# bikeSensor.net
KiCad netlist of a schematic drawn in EAGLE
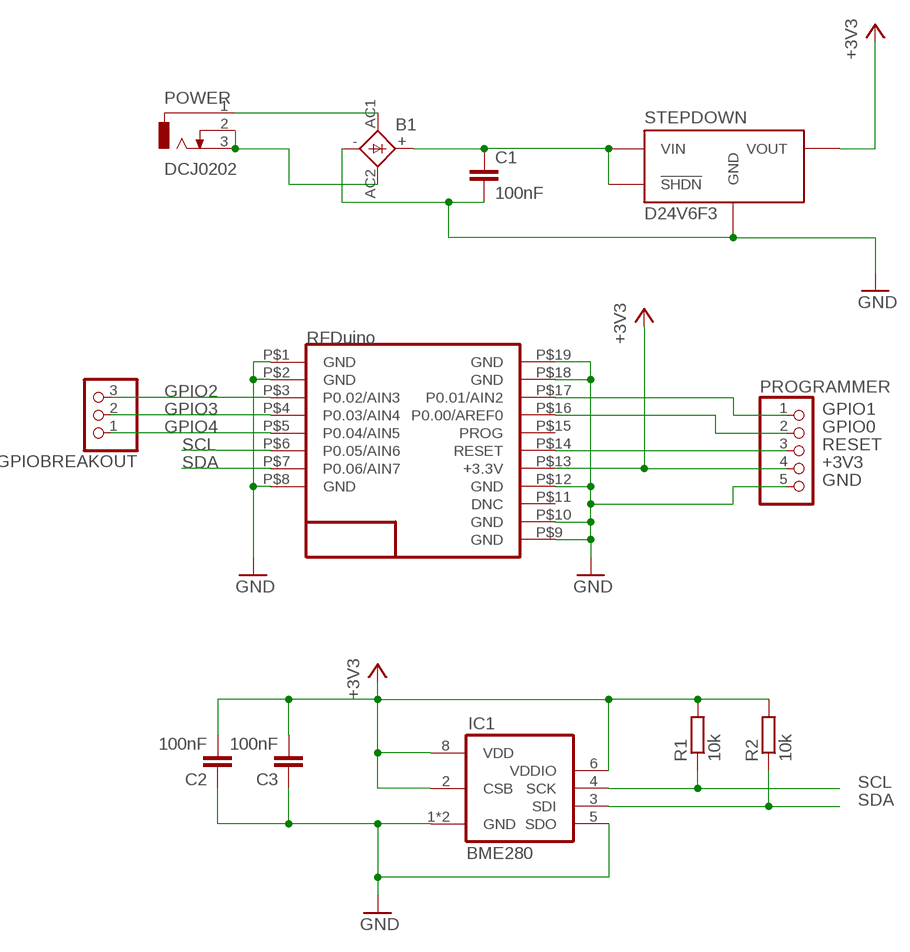
[diagram p0: schematic, sheet 1]

(export (version "E")
  (design (tool "Eeschema 10.0.6"))
  (components
    (comp (ref "B1")
      (value "1KAB")
      (footprint "eagle-import:1KAB")
      (libsource (lib "eagle-import") (part "1KAB"))
    )
    (comp (ref "C1")
      (value "100nF")
      (footprint "eagle-import:C025-050X050")
      (libsource (lib "eagle-import") (part "C-EU025-050X050"))
    )
    (comp (ref "C2")
      (value "100nF")
      (footprint "eagle-import:C1812")
      (libsource (lib "eagle-import") (part "C-EUC1812"))
    )
    (comp (ref "C3")
      (value "100nF")
      (footprint "eagle-import:C1812")
      (libsource (lib "eagle-import") (part "C-EUC1812"))
    )
    (comp (ref "GPIOBREAKOUT")
      (value "PINHD-1X3")
      (footprint "eagle-import:1X03")
      (libsource (lib "eagle-import") (part "PINHD-1X3"))
    )
    (comp (ref "IC1")
      (value "BME280")
      (footprint "eagle-import:BME280")
      (libsource (lib "eagle-import") (part "BME280"))
    )
    (comp (ref "POWER")
      (value "DCJ0202")
      (footprint "eagle-import:DCJ0202")
      (libsource (lib "eagle-import") (part "DCJ0202"))
    )
    (comp (ref "PROGRAMMER")
      (value "PINHD-1X5")
      (footprint "eagle-import:1X05")
      (libsource (lib "eagle-import") (part "PINHD-1X5"))
    )
    (comp (ref "R1")
      (value "10k")
      (footprint "eagle-import:R1206")
      (libsource (lib "eagle-import") (part "R-EU_R1206"))
    )
    (comp (ref "R2")
      (value "10k")
      (footprint "eagle-import:R1206")
      (libsource (lib "eagle-import") (part "R-EU_R1206"))
    )
    (comp (ref "RFDUINO")
      (value "RFD22301")
      (footprint "eagle-import:RFD21733")
      (libsource (lib "eagle-import") (part "RFD22301"))
    )
    (comp (ref "STEPDOWN")
      (value "D24V6F3")
      (footprint "eagle-import:D24V6F3")
      (libsource (lib "eagle-import") (part "D24V6F3"))
    )
  )
  (nets
    (net (code "1") (name "+3V3") (class "Default")
      (node (ref "C2") (pin "2") (pinfunction "2_2") (pintype "passive"))
      (node (ref "C3") (pin "2") (pinfunction "2_2") (pintype "passive"))
      (node (ref "IC1") (pin "2") (pinfunction "CSB_2") (pintype "input"))
      (node (ref "IC1") (pin "6") (pinfunction "VDDIO_6") (pintype "power_in"))
      (node (ref "IC1") (pin "8") (pinfunction "VDD_8") (pintype "power_in"))
      (node (ref "PROGRAMMER") (pin "4") (pinfunction "4_4") (pintype "passive"))
      (node (ref "R1") (pin "2") (pinfunction "2_2") (pintype "passive"))
      (node (ref "R2") (pin "2") (pinfunction "2_2") (pintype "passive"))
      (node (ref "RFDUINO") (pin "P$13") (pinfunction "+3.3V_P$13") (pintype "bidirectional"))
      (node (ref "STEPDOWN") (pin "VOUT") (pinfunction "VOUT_VOUT") (pintype "bidirectional"))
    )
    (net (code "2") (name "/GPIO0") (class "Default")
      (node (ref "PROGRAMMER") (pin "2") (pinfunction "2_2") (pintype "passive"))
      (node (ref "RFDUINO") (pin "P$16") (pinfunction "P0.00/AREF0_P$16") (pintype "bidirectional"))
    )
    (net (code "3") (name "/GPIO1") (class "Default")
      (node (ref "PROGRAMMER") (pin "1") (pinfunction "1_1") (pintype "passive"))
      (node (ref "RFDUINO") (pin "P$17") (pinfunction "P0.01/AIN2_P$17") (pintype "bidirectional"))
    )
    (net (code "4") (name "/GPIO2") (class "Default")
      (node (ref "GPIOBREAKOUT") (pin "3") (pinfunction "3_3") (pintype "passive"))
      (node (ref "RFDUINO") (pin "P$3") (pinfunction "P0.02/AIN3_P$3") (pintype "bidirectional"))
    )
    (net (code "5") (name "/GPIO3") (class "Default")
      (node (ref "GPIOBREAKOUT") (pin "2") (pinfunction "2_2") (pintype "passive"))
      (node (ref "RFDUINO") (pin "P$4") (pinfunction "P0.03/AIN4_P$4") (pintype "bidirectional"))
    )
    (net (code "6") (name "/GPIO4") (class "Default")
      (node (ref "GPIOBREAKOUT") (pin "1") (pinfunction "1_1") (pintype "passive"))
      (node (ref "RFDUINO") (pin "P$5") (pinfunction "P0.04/AIN5_P$5") (pintype "bidirectional"))
    )
    (net (code "7") (name "/RESET") (class "Default")
      (node (ref "PROGRAMMER") (pin "3") (pinfunction "3_3") (pintype "passive"))
      (node (ref "RFDUINO") (pin "P$14") (pinfunction "RESET_P$14") (pintype "bidirectional"))
    )
    (net (code "8") (name "/SCL") (class "Default")
      (node (ref "IC1") (pin "4") (pinfunction "SCK_4") (pintype "bidirectional"))
      (node (ref "R1") (pin "1") (pinfunction "1_1") (pintype "passive"))
      (node (ref "RFDUINO") (pin "P$6") (pinfunction "P0.05/AIN6_P$6") (pintype "bidirectional"))
    )
    (net (code "9") (name "/SDA") (class "Default")
      (node (ref "IC1") (pin "3") (pinfunction "SDI_3") (pintype "bidirectional"))
      (node (ref "R2") (pin "1") (pinfunction "1_1") (pintype "passive"))
      (node (ref "RFDUINO") (pin "P$7") (pinfunction "P0.06/AIN7_P$7") (pintype "bidirectional"))
    )
    (net (code "10") (name "GND") (class "Default")
      (node (ref "B1") (pin "-") (pinfunction "-_-") (pintype "passive"))
      (node (ref "C1") (pin "2") (pinfunction "2_2") (pintype "passive"))
      (node (ref "C2") (pin "1") (pinfunction "1_1") (pintype "passive"))
      (node (ref "C3") (pin "1") (pinfunction "1_1") (pintype "passive"))
      (node (ref "IC1") (pin "1") (pinfunction "GND_1") (pintype "power_in"))
      (node (ref "IC1") (pin "5") (pinfunction "SDO_5") (pintype "input"))
      (node (ref "IC1") (pin "7") (pinfunction "GND_7") (pintype "power_in"))
      (node (ref "PROGRAMMER") (pin "5") (pinfunction "5_5") (pintype "passive"))
      (node (ref "RFDUINO") (pin "P$1") (pinfunction "GND_P$1") (pintype "bidirectional"))
      (node (ref "RFDUINO") (pin "P$10") (pinfunction "GND_P$10") (pintype "bidirectional"))
      (node (ref "RFDUINO") (pin "P$12") (pinfunction "GND_P$12") (pintype "bidirectional"))
      (node (ref "RFDUINO") (pin "P$18") (pinfunction "GND_P$18") (pintype "bidirectional"))
      (node (ref "RFDUINO") (pin "P$19") (pinfunction "GND_P$19") (pintype "bidirectional"))
      (node (ref "RFDUINO") (pin "P$2") (pinfunction "GND_P$2") (pintype "bidirectional"))
      (node (ref "RFDUINO") (pin "P$8") (pinfunction "GND_P$8") (pintype "bidirectional"))
      (node (ref "RFDUINO") (pin "P$9") (pinfunction "GND_P$9") (pintype "bidirectional"))
      (node (ref "STEPDOWN") (pin "GND") (pinfunction "GND_GND") (pintype "bidirectional"))
    )
    (net (code "11") (name "Net-(B1-PadAC1)") (class "Default")
      (node (ref "B1") (pin "AC1") (pinfunction "AC1_AC1") (pintype "passive"))
      (node (ref "POWER") (pin "1") (pinfunction "1_1") (pintype "passive"))
    )
    (net (code "12") (name "Net-(B1-PadAC2)") (class "Default")
      (node (ref "B1") (pin "AC2") (pinfunction "AC2_AC2") (pintype "passive"))
      (node (ref "POWER") (pin "2") (pinfunction "2_2") (pintype "passive"))
      (node (ref "POWER") (pin "3") (pinfunction "3_3") (pintype "passive"))
    )
    (net (code "13") (name "Net-(STEPDOWN-~{SHDN})") (class "Default")
      (node (ref "B1") (pin "+") (pinfunction "+_+") (pintype "passive"))
      (node (ref "C1") (pin "1") (pinfunction "1_1") (pintype "passive"))
      (node (ref "STEPDOWN") (pin "!SHDN") (pinfunction "~{SHDN}_!SHDN") (pintype "bidirectional"))
      (node (ref "STEPDOWN") (pin "VIN") (pinfunction "VIN_VIN") (pintype "bidirectional"))
    )
    (net (code "14") (name "unconnected-(RFDUINO-DNC-PadP$11)") (class "Default")
      (node (ref "RFDUINO") (pin "P$11") (pinfunction "DNC_P$11") (pintype "bidirectional"))
    )
    (net (code "15") (name "unconnected-(RFDUINO-PROG-PadP$15)") (class "Default")
      (node (ref "RFDUINO") (pin "P$15") (pinfunction "PROG_P$15") (pintype "bidirectional"))
    )
  )
)
